# ProDoc_Relay_2025-09-14.net
KiCad netlist of a schematic drawn in EasyEDA Pro
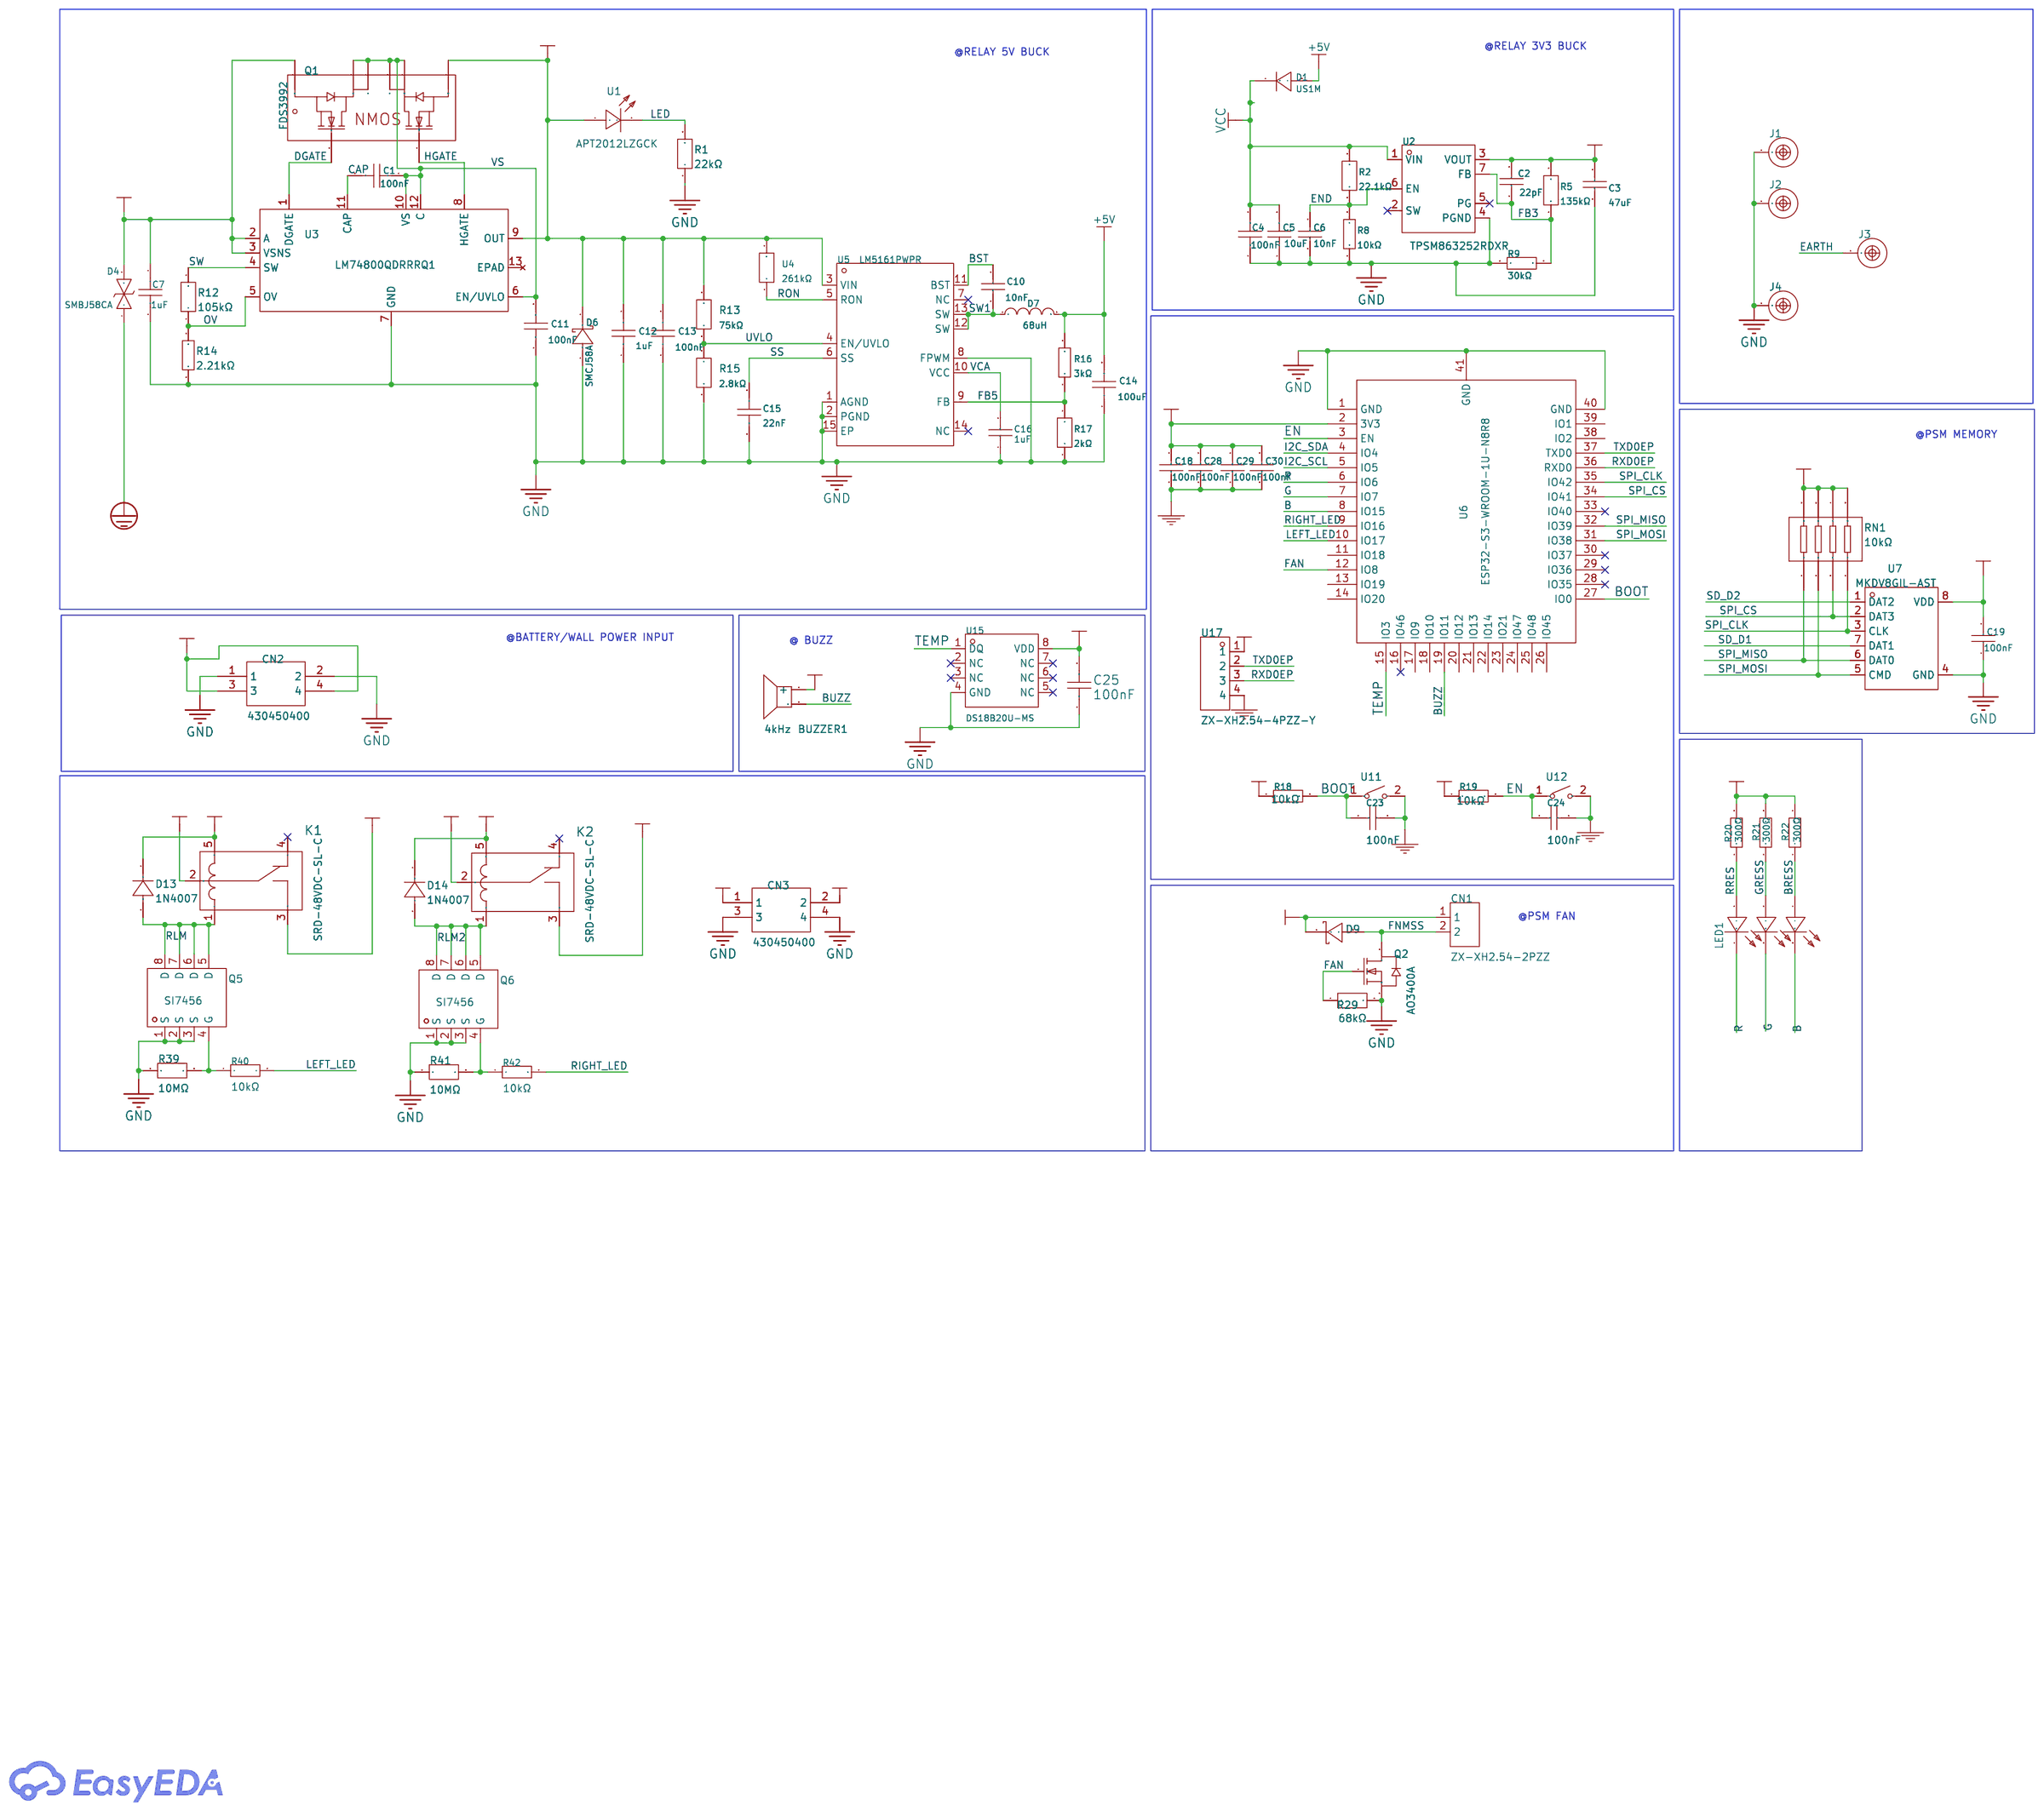
[diagram p0: schematic sheet]

(export (version "E")
  (design (tool "Eeschema 10.0.6"))
  (components
    (comp (ref "BUZZER1")
      (value "4kHz")
      (footprint "easyedapro:BUZ-TH_PKM13EPYH4002-B0")
      (fields
        (field (name "Manufacturer Part") "PKM13EPYH4002-B0")
        (field (name "Manufacturer") "muRata(村田)")
      )
      (libsource (lib "easyedapro") (part "PKM13EPYH4002-B0"))
    )
    (comp (ref "C1")
      (value "100nF")
      (footprint "easyedapro:C1210")
      (fields
        (field (name "Manufacturer Part") "CC1210KKX7RYBB104")
        (field (name "Manufacturer") "YAGEO(国巨)")
      )
      (libsource (lib "easyedapro") (part "CC1210KKX7RYBB104"))
    )
    (comp (ref "C2")
      (value "22pF")
      (footprint "easyedapro:C0201")
      (fields
        (field (name "Manufacturer Part") "GRM0335C1E220JA01D")
        (field (name "Manufacturer") "muRata(村田)")
      )
      (libsource (lib "easyedapro") (part "GRM0335C1E220JA01D"))
    )
    (comp (ref "C3")
      (value "47uF")
      (footprint "easyedapro:C1210")
      (fields
        (field (name "Manufacturer Part") "GRM32ER71A476KE15L")
        (field (name "Manufacturer") "muRata(村田)")
      )
      (libsource (lib "easyedapro") (part "GRM32ER71A476KE15L"))
    )
    (comp (ref "C4")
      (value "100nF")
      (footprint "easyedapro:C0402")
      (fields
        (field (name "Manufacturer Part") "GRM155R71A104KA01D")
        (field (name "Manufacturer") "muRata(村田)")
      )
      (libsource (lib "easyedapro") (part "GRM155R71A104KA01D"))
    )
    (comp (ref "C5")
      (value "10uF")
      (footprint "easyedapro:C0805")
      (fields (field (name "Manufacturer Part") "C0805C106K8PACTU") (field (name "Manufacturer") "KEMET(基美)"))
      (libsource (lib "easyedapro") (part "C0805C106K8PACTU"))
    )
    (comp (ref "C6")
      (value "10nF")
      (footprint "easyedapro:C0201")
      (fields
        (field (name "Manufacturer Part") "GRM033R70J103KA01D")
        (field (name "Manufacturer") "muRata(村田)")
      )
      (libsource (lib "easyedapro") (part "GRM033R70J103KA01D"))
    )
    (comp (ref "C7")
      (value "1uF")
      (footprint "easyedapro:C2220")
      (fields
        (field (name "Manufacturer Part") "GRM55DR72E105KW01L")
        (field (name "Manufacturer") "muRata(村田)")
      )
      (libsource (lib "easyedapro") (part "GRM55DR72E105KW01L"))
    )
    (comp (ref "C10")
      (value "10nF")
      (footprint "easyedapro:C0402")
      (fields
        (field (name "Manufacturer Part") "GRM155R71H103KA88D")
        (field (name "Manufacturer") "muRata(村田)")
      )
      (libsource (lib "easyedapro") (part "GRM155R71H103KA88D"))
    )
    (comp (ref "C11")
      (value "100nF")
      (footprint "easyedapro:C1210")
      (fields
        (field (name "Manufacturer Part") "CC1210KKX7RYBB104")
        (field (name "Manufacturer") "YAGEO(国巨)")
      )
      (libsource (lib "easyedapro") (part "CC1210KKX7RYBB104"))
    )
    (comp (ref "C12")
      (value "1uF")
      (footprint "easyedapro:C2220")
      (fields
        (field (name "Manufacturer Part") "GRM55DR72E105KW01L")
        (field (name "Manufacturer") "muRata(村田)")
      )
      (libsource (lib "easyedapro") (part "GRM55DR72E105KW01L"))
    )
    (comp (ref "C13")
      (value "100nF")
      (footprint "easyedapro:C1210")
      (fields
        (field (name "Manufacturer Part") "CC1210KKX7RYBB104")
        (field (name "Manufacturer") "YAGEO(国巨)")
      )
      (libsource (lib "easyedapro") (part "CC1210KKX7RYBB104"))
    )
    (comp (ref "C14")
      (value "100uF")
      (footprint "easyedapro:C1210")
      (fields
        (field (name "Manufacturer Part") "GRM32ER60J107ME20L")
        (field (name "Manufacturer") "muRata(村田)")
      )
      (libsource (lib "easyedapro") (part "GRM32ER60J107ME20L"))
    )
    (comp (ref "C15")
      (value "22nF")
      (footprint "easyedapro:C0805")
      (fields
        (field (name "Manufacturer Part") "CC0805KRX7R7BB223")
        (field (name "Manufacturer") "YAGEO(国巨)")
      )
      (libsource (lib "easyedapro") (part "CC0805KRX7R7BB223"))
    )
    (comp (ref "C16")
      (value "1uF")
      (footprint "easyedapro:C0603")
      (description "Capacitance:1uF Tolerance:±10% Tolerance:±10% Voltage Rating:16V Temperature Coefficient:X7R")
      (fields
        (field (name "Manufacturer Part") "EMK107B7105KA-T")
        (field (name "Manufacturer") "TAIYO YUDEN(太诱)")
      )
      (libsource (lib "easyedapro") (part "EMK107B7105KA-T"))
    )
    (comp (ref "C18")
      (value "100nF")
      (footprint "easyedapro:C0805")
      (fields (field (name "Manufacturer Part") "0805B104K500NT") (field (name "Manufacturer") "FH(风华)"))
      (libsource (lib "easyedapro") (part "0805B104K500NT"))
    )
    (comp (ref "C19")
      (value "100nF")
      (footprint "easyedapro:C0805")
      (fields (field (name "Manufacturer Part") "0805B104K500NT") (field (name "Manufacturer") "FH(风华)"))
      (libsource (lib "easyedapro") (part "0805B104K500NT"))
    )
    (comp (ref "C23")
      (value "100nF")
      (footprint "easyedapro:C0805")
      (fields (field (name "Manufacturer Part") "0805B104K500NT") (field (name "Manufacturer") "FH(风华)"))
      (libsource (lib "easyedapro") (part "0805B104K500NT"))
    )
    (comp (ref "C24")
      (value "100nF")
      (footprint "easyedapro:C0805")
      (fields (field (name "Manufacturer Part") "0805B104K500NT") (field (name "Manufacturer") "FH(风华)"))
      (libsource (lib "easyedapro") (part "0805B104K500NT"))
    )
    (comp (ref "C25")
      (value "100nF")
      (footprint "easyedapro:C0805")
      (description "Capacitance:0.1uF Tolerance:±10% Tolerance:±10% Voltage Rating:50V Temperature Coefficient:X7R")
      (fields
        (field (name "Manufacturer Part") "GCM21BR71H104KA37K")
        (field (name "Manufacturer") "muRata(村田)")
      )
      (libsource (lib "easyedapro") (part "GCM21BR71H104KA37K"))
    )
    (comp (ref "C28")
      (value "100nF")
      (footprint "easyedapro:C0805")
      (fields (field (name "Manufacturer Part") "0805B104K500NT") (field (name "Manufacturer") "FH(风华)"))
      (libsource (lib "easyedapro") (part "0805B104K500NT"))
    )
    (comp (ref "C29")
      (value "100nF")
      (footprint "easyedapro:C0805")
      (fields (field (name "Manufacturer Part") "0805B104K500NT") (field (name "Manufacturer") "FH(风华)"))
      (libsource (lib "easyedapro") (part "0805B104K500NT"))
    )
    (comp (ref "C30")
      (value "100nF")
      (footprint "easyedapro:C0805")
      (fields (field (name "Manufacturer Part") "0805B104K500NT") (field (name "Manufacturer") "FH(风华)"))
      (libsource (lib "easyedapro") (part "0805B104K500NT"))
    )
    (comp (ref "CN1")
      (value "ZX-XH2.54-2PZZ")
      (footprint "easyedapro:CONN-TH_2P-P2.50_HX25003-2A")
      (fields (field (name "Manufacturer") "Megastar(兆星)"))
      (libsource (lib "easyedapro") (part "ZX-XH2.54-2PZZ"))
    )
    (comp (ref "CN2")
      (value "430450400")
      (footprint "easyedapro:CONN-TH_0430450400")
      (fields (field (name "Manufacturer") "MOLEX"))
      (libsource (lib "easyedapro") (part "0430450400"))
    )
    (comp (ref "CN3")
      (value "430450400")
      (footprint "easyedapro:CONN-TH_0430450400")
      (fields (field (name "Manufacturer") "MOLEX"))
      (libsource (lib "easyedapro") (part "0430450400"))
    )
    (comp (ref "D1")
      (value "US1M")
      (footprint "easyedapro:SMA_L4.4-W2.8-LS5.4-RD")
      (fields (field (name "Manufacturer") "MDD(辰达半导体)"))
      (libsource (lib "easyedapro") (part "US1MG_C412437"))
    )
    (comp (ref "D4")
      (value "SMBJ58CA")
      (footprint "easyedapro:SMB_L4.6-W3.6-LS5.3-BI")
      (fields (field (name "Manufacturer") "AnBon(安邦)"))
      (libsource (lib "easyedapro") (part "SMBJ58CA_C440309"))
    )
    (comp (ref "D6")
      (value "SMCJ58A")
      (footprint "easyedapro:SMC_L6.9-W5.8-LS7.9-RD")
      (fields (field (name "Manufacturer") "宏嘉诚"))
      (libsource (lib "easyedapro") (part "SMCJ58A_C42371547"))
    )
    (comp (ref "D7")
      (value "68uH")
      (footprint "easyedapro:IND-SMD_L12.5-W12.5-SRR1280-150M")
      (fields (field (name "Manufacturer Part") "SRR1260-680M") (field (name "Manufacturer") "BOURNS"))
      (libsource (lib "easyedapro") (part "SRR1260-680M"))
    )
    (comp (ref "D9")
      (value "BAT46WJ,115")
      (footprint "easyedapro:SOD-323F_L2.0-W1.6-LS2.5-RD")
      (fields (field (name "Manufacturer") "Nexperia(安世)"))
      (libsource (lib "easyedapro") (part "BAT46WJ,115"))
    )
    (comp (ref "D13")
      (value "1N4007")
      (footprint "easyedapro:SMA_L4.3-W2.5-LS5.0-RD")
      (fields (field (name "Manufacturer") "TWGMC(迪嘉)"))
      (libsource (lib "easyedapro") (part "1N4007_C727081"))
    )
    (comp (ref "D14")
      (value "1N4007")
      (footprint "easyedapro:SMA_L4.3-W2.5-LS5.0-RD")
      (fields (field (name "Manufacturer") "TWGMC(迪嘉)"))
      (libsource (lib "easyedapro") (part "1N4007_C727081"))
    )
    (comp (ref "J1")
      (value "SCREW-MOUNTING-HOLE-3MM")
      (libsource (lib "easyedapro") (part "SCREW-MOUNTING-HOLE-3MM"))
    )
    (comp (ref "J2")
      (value "SCREW-MOUNTING-HOLE-3MM")
      (libsource (lib "easyedapro") (part "SCREW-MOUNTING-HOLE-3MM"))
    )
    (comp (ref "J3")
      (value "SCREW-MOUNTING-HOLE-3MM")
      (libsource (lib "easyedapro") (part "SCREW-MOUNTING-HOLE-3MM"))
    )
    (comp (ref "J4")
      (value "SCREW-MOUNTING-HOLE-3MM")
      (libsource (lib "easyedapro") (part "SCREW-MOUNTING-HOLE-3MM"))
    )
    (comp (ref "K1")
      (value "SRD-48VDC-SL-C")
      (footprint "easyedapro:RELAY-TH_SRD-48VDC-SL-C")
      (fields (field (name "Manufacturer") "松乐"))
      (libsource (lib "easyedapro") (part "SRD-48VDC-SL-C"))
    )
    (comp (ref "K2")
      (value "SRD-48VDC-SL-C")
      (footprint "easyedapro:RELAY-TH_SRD-48VDC-SL-C")
      (fields (field (name "Manufacturer") "松乐"))
      (libsource (lib "easyedapro") (part "SRD-48VDC-SL-C"))
    )
    (comp (ref "LED1")
      (value "HL-AF-5060H271BU46FU79GC-S1-THL")
      (footprint "easyedapro:LED-ARRAY-SMD_6P-L5.4-W5.0-TL-FD")
      (fields (field (name "Manufacturer") "HONGLITRONIC(鸿利光电)"))
      (libsource (lib "easyedapro") (part "HL-AF-5060H271BU46FU79GC-S1-THL"))
    )
    (comp (ref "Q1")
      (value "FDS3992")
      (footprint "easyedapro:SO-8_L4.9-W3.9-P1.27-LS5.9-BL")
      (fields (field (name "Manufacturer") "onsemi(安森美)"))
      (libsource (lib "easyedapro") (part "FDS3992"))
    )
    (comp (ref "Q2")
      (value "AO3400A")
      (footprint "easyedapro:SOT-23-3_L2.9-W1.6-P1.90-LS2.8-BR")
      (fields (field (name "Manufacturer") "MSKSEMI(美森科)"))
      (libsource (lib "easyedapro") (part "AO3400A_C5379092"))
    )
    (comp (ref "Q5")
      (value "SI7456")
      (footprint "easyedapro:POWERPAK-SO-8_L5.9-W4.9-P1.27-LS6.2-BL")
      (fields (field (name "Manufacturer") "VISHAY(威世)"))
      (libsource (lib "easyedapro") (part "SI7456DP-T1-GE3"))
    )
    (comp (ref "Q6")
      (value "SI7456")
      (footprint "easyedapro:POWERPAK-SO-8_L5.9-W4.9-P1.27-LS6.2-BL")
      (fields (field (name "Manufacturer") "VISHAY(威世)"))
      (libsource (lib "easyedapro") (part "SI7456DP-T1-GE3"))
    )
    (comp (ref "R1")
      (value "22kΩ")
      (footprint "easyedapro:R1210")
      (fields (field (name "Manufacturer Part") "AC1210FR-0722KL") (field (name "Manufacturer") "YAGEO(国巨)"))
      (libsource (lib "easyedapro") (part "AC1210FR-0722KL"))
    )
    (comp (ref "R2")
      (value "22.1kΩ")
      (footprint "easyedapro:R0402")
      (fields
        (field (name "Manufacturer Part") "CRCW040222K1FKED")
        (field (name "Manufacturer") "VISHAY(威世)")
      )
      (libsource (lib "easyedapro") (part "CRCW040222K1FKED"))
    )
    (comp (ref "R5")
      (value "135kΩ")
      (footprint "easyedapro:R0603")
      (fields (field (name "Manufacturer Part") "RT0603BRD07135KL") (field (name "Manufacturer") "YAGEO(国巨)"))
      (libsource (lib "easyedapro") (part "RT0603BRD07135KL"))
    )
    (comp (ref "R8")
      (value "10kΩ")
      (footprint "easyedapro:R0402")
      (fields
        (field (name "Manufacturer Part") "CRCW040210K0FKED")
        (field (name "Manufacturer") "VISHAY(威世)")
      )
      (libsource (lib "easyedapro") (part "CRCW040210K0FKED"))
    )
    (comp (ref "R9")
      (value "30kΩ")
      (footprint "easyedapro:R0603")
      (fields (field (name "Manufacturer Part") "RC0603FR-0730KL") (field (name "Manufacturer") "YAGEO(国巨)"))
      (libsource (lib "easyedapro") (part "RC0603FR-0730KL"))
    )
    (comp (ref "R12")
      (value "105kΩ")
      (footprint "easyedapro:R1206")
      (fields (field (name "Manufacturer Part") "RC1206FR-07105KL") (field (name "Manufacturer") "YAGEO(国巨)"))
      (libsource (lib "easyedapro") (part "RC1206FR-07105KL"))
    )
    (comp (ref "R13")
      (value "75kΩ")
      (footprint "easyedapro:R1210")
      (fields (field (name "Manufacturer Part") "AC1210FR-0775KL") (field (name "Manufacturer") "YAGEO(国巨)"))
      (libsource (lib "easyedapro") (part "AC1210FR-0775KL"))
    )
    (comp (ref "R14")
      (value "2.21kΩ")
      (footprint "easyedapro:R1206")
      (fields (field (name "Manufacturer Part") "AC1206FR-072K21L") (field (name "Manufacturer") "YAGEO(国巨)"))
      (libsource (lib "easyedapro") (part "AC1206FR-072K21L"))
    )
    (comp (ref "R15")
      (value "2.8kΩ")
      (footprint "easyedapro:R1210")
      (fields (field (name "Manufacturer Part") "AC1210FR-072K8L") (field (name "Manufacturer") "YAGEO(国巨)"))
      (libsource (lib "easyedapro") (part "AC1210FR-072K8L"))
    )
    (comp (ref "R16")
      (value "3kΩ")
      (footprint "easyedapro:R0603")
      (fields (field (name "Manufacturer Part") "RC0603FR-073KL") (field (name "Manufacturer") "YAGEO(国巨)"))
      (libsource (lib "easyedapro") (part "RC0603FR-073KL"))
    )
    (comp (ref "R17")
      (value "2kΩ")
      (footprint "easyedapro:R0402")
      (fields
        (field (name "Manufacturer Part") "CRCW04022K00FKED")
        (field (name "Manufacturer") "VISHAY(威世)")
      )
      (libsource (lib "easyedapro") (part "CRCW04022K00FKED"))
    )
    (comp (ref "R18")
      (value "10kΩ")
      (footprint "easyedapro:R0805")
      (fields
        (field (name "Manufacturer Part") "0805W8F1002T5E")
        (field (name "Manufacturer") "UNI-ROYAL(厚声)")
      )
      (libsource (lib "easyedapro") (part "0805W8F1002T5E"))
    )
    (comp (ref "R19")
      (value "10kΩ")
      (footprint "easyedapro:R0805")
      (fields
        (field (name "Manufacturer Part") "0805W8F1002T5E")
        (field (name "Manufacturer") "UNI-ROYAL(厚声)")
      )
      (libsource (lib "easyedapro") (part "0805W8F1002T5E"))
    )
    (comp (ref "R20")
      (value "300Ω")
      (footprint "easyedapro:R0805")
      (fields
        (field (name "Manufacturer Part") "0805W8F3000T5E")
        (field (name "Manufacturer") "UNI-ROYAL(厚声)")
      )
      (libsource (lib "easyedapro") (part "0805W8F3000T5E"))
    )
    (comp (ref "R21")
      (value "300Ω")
      (footprint "easyedapro:R0805")
      (fields
        (field (name "Manufacturer Part") "0805W8F3000T5E")
        (field (name "Manufacturer") "UNI-ROYAL(厚声)")
      )
      (libsource (lib "easyedapro") (part "0805W8F3000T5E"))
    )
    (comp (ref "R22")
      (value "300Ω")
      (footprint "easyedapro:R0805")
      (fields
        (field (name "Manufacturer Part") "0805W8F3000T5E")
        (field (name "Manufacturer") "UNI-ROYAL(厚声)")
      )
      (libsource (lib "easyedapro") (part "0805W8F3000T5E"))
    )
    (comp (ref "R29")
      (value "68kΩ")
      (footprint "easyedapro:R1206")
      (fields (field (name "Manufacturer Part") "RT1206BRD0768KL") (field (name "Manufacturer") "YAGEO(国巨)"))
      (libsource (lib "easyedapro") (part "RT1206BRD0768KL"))
    )
    (comp (ref "R39")
      (value "10MΩ")
      (footprint "easyedapro:R1206")
      (fields (field (name "Manufacturer Part") "FRC1206F1005TS") (field (name "Manufacturer") "FOJAN(富捷)"))
      (libsource (lib "easyedapro") (part "FRC1206F1005TS"))
    )
    (comp (ref "R40")
      (value "10kΩ")
      (footprint "easyedapro:R1206")
      (fields
        (field (name "Manufacturer Part") "1206W4F1002T5E")
        (field (name "Manufacturer") "UNI-ROYAL(厚声)")
      )
      (libsource (lib "easyedapro") (part "1206W4F1002T5E"))
    )
    (comp (ref "R41")
      (value "10MΩ")
      (footprint "easyedapro:R1206")
      (fields (field (name "Manufacturer Part") "FRC1206F1005TS") (field (name "Manufacturer") "FOJAN(富捷)"))
      (libsource (lib "easyedapro") (part "FRC1206F1005TS"))
    )
    (comp (ref "R42")
      (value "10kΩ")
      (footprint "easyedapro:R1206")
      (fields
        (field (name "Manufacturer Part") "1206W4F1002T5E")
        (field (name "Manufacturer") "UNI-ROYAL(厚声)")
      )
      (libsource (lib "easyedapro") (part "1206W4F1002T5E"))
    )
    (comp (ref "RN1")
      (value "10kΩ")
      (footprint "easyedapro:RES-ARRAY-SMD_0603-8P-L3.2-W1.6-BL")
      (fields
        (field (name "Manufacturer Part") "4D03WGJ0103T5E")
        (field (name "Manufacturer") "UNI-ROYAL(厚声)")
      )
      (libsource (lib "easyedapro") (part "4D03WGJ0103T5E"))
    )
    (comp (ref "U1")
      (value "APT2012LZGCK")
      (footprint "easyedapro:LED-SMD_L2.0-W1.3-R-RD")
      (fields (field (name "Manufacturer") "Kingbright"))
      (libsource (lib "easyedapro") (part "APT2012LZGCK"))
    )
    (comp (ref "U2")
      (value "TPSM863252RDXR")
      (footprint "easyedapro:QFN-7_L4.0-W3.3_TPSM863257RDXR")
      (fields (field (name "Manufacturer") "TI(德州仪器)"))
      (libsource (lib "easyedapro") (part "TPSM863252RDXR"))
    )
    (comp (ref "U3")
      (value "LM74800QDRRRQ1")
      (footprint "easyedapro:WSON-12_L3.0-W3.0-P0.50-TL-EP-2")
      (fields (field (name "Manufacturer") "TI(德州仪器)"))
      (libsource (lib "easyedapro") (part "LM74800QDRRRQ1"))
    )
    (comp (ref "U4")
      (value "261kΩ")
      (footprint "easyedapro:R0402")
      (fields
        (field (name "Manufacturer Part") "CRCW0402261KFKED")
        (field (name "Manufacturer") "VISHAY(威世)")
      )
      (libsource (lib "easyedapro") (part "CRCW0402261KFKED"))
    )
    (comp (ref "U5")
      (value "LM5161PWPR")
      (footprint "easyedapro:HTSSOP-14_L5.0-W4.4-P0.65-LS6.4-BL-EP3.0")
      (fields (field (name "Manufacturer") "TI(德州仪器)"))
      (libsource (lib "easyedapro") (part "LM5161PWPR"))
    )
    (comp (ref "U6")
      (value "ESP32-S3-WROOM-1U-N8R8")
      (footprint "easyedapro:WIRELM-SMD_ESP32-S3-WROOM-1U")
      (fields (field (name "Manufacturer") "ESPRESSIF(乐鑫)"))
      (libsource (lib "easyedapro") (part "ESP32-S3-WROOM-1U-N8R8"))
    )
    (comp (ref "U7")
      (value "MKDV8GIL-AST")
      (footprint "easyedapro:LGA-8_L6.0-W8.0-P1.27-TL")
      (fields (field (name "Manufacturer") "MK(米客方德)"))
      (libsource (lib "easyedapro") (part "MKDV8GIL-AST"))
    )
    (comp (ref "U11") (value "TD-1183SN-1.7H-250") (libsource (lib "easyedapro") (part "TD-1183SN-1.7H-250")))
    (comp (ref "U12") (value "TD-1183SN-1.7H-250") (libsource (lib "easyedapro") (part "TD-1183SN-1.7H-250")))
    (comp (ref "U15")
      (value "DS18B20U-MS")
      (footprint "easyedapro:MSOP-8_L3.0-W3.0-P0.65-LS4.9-BL-1")
      (fields (field (name "Manufacturer") "MSKSEMI(美森科)"))
      (libsource (lib "easyedapro") (part "DS18B20U-MS"))
    )
    (comp (ref "U17")
      (value "ZX-XH2.54-4PZZ-Y")
      (footprint "easyedapro:CONN-TH_4P-P2.50_ZX-XH2.54-4PZZ-Y")
      (fields (field (name "Manufacturer") "Megastar(兆星)"))
      (libsource (lib "easyedapro") (part "ZX-XH2.54-4PZZ-Y"))
    )
  )
  (nets
    (net (code "1") (name "+3V3") (class "Default")
      (node (ref "BUZZER1") (pin "1") (pinfunction "+_1") (pintype "unspecified"))
      (node (ref "C18") (pin "2") (pinfunction "2_2") (pintype "input"))
      (node (ref "C19") (pin "2") (pinfunction "2_2") (pintype "input"))
      (node (ref "C2") (pin "2") (pinfunction "2_2") (pintype "input"))
      (node (ref "C25") (pin "2") (pinfunction "2_2") (pintype "unspecified"))
      (node (ref "C28") (pin "2") (pinfunction "2_2") (pintype "input"))
      (node (ref "C29") (pin "2") (pinfunction "2_2") (pintype "input"))
      (node (ref "C3") (pin "2") (pinfunction "2_2") (pintype "input"))
      (node (ref "C30") (pin "2") (pinfunction "2_2") (pintype "input"))
      (node (ref "R18") (pin "1") (pinfunction "1_1") (pintype "input"))
      (node (ref "R19") (pin "1") (pinfunction "1_1") (pintype "input"))
      (node (ref "R20") (pin "2") (pinfunction "2_2") (pintype "input"))
      (node (ref "R21") (pin "2") (pinfunction "2_2") (pintype "input"))
      (node (ref "R22") (pin "2") (pinfunction "2_2") (pintype "input"))
      (node (ref "R5") (pin "2") (pinfunction "2_2") (pintype "unspecified"))
      (node (ref "RN1") (pin "5") (pinfunction "5_5") (pintype "input"))
      (node (ref "RN1") (pin "6") (pinfunction "6_6") (pintype "input"))
      (node (ref "RN1") (pin "7") (pinfunction "7_7") (pintype "input"))
      (node (ref "RN1") (pin "8") (pinfunction "8_8") (pintype "input"))
      (node (ref "U15") (pin "8") (pinfunction "VDD_8") (pintype "unspecified"))
      (node (ref "U17") (pin "1") (pinfunction "1_1") (pintype "unspecified"))
      (node (ref "U2") (pin "3") (pinfunction "VOUT_3") (pintype "unspecified"))
      (node (ref "U6") (pin "2") (pinfunction "3V3_2") (pintype "unspecified"))
      (node (ref "U7") (pin "8") (pinfunction "VDD_8") (pintype "unspecified"))
    )
    (net (code "2") (name "+5V") (class "Default")
      (node (ref "C14") (pin "2") (pinfunction "2_2") (pintype "input"))
      (node (ref "D1") (pin "2") (pinfunction "A_2") (pintype "unspecified"))
      (node (ref "D7") (pin "2") (pinfunction "2_2") (pintype "unspecified"))
      (node (ref "R16") (pin "2") (pinfunction "2_2") (pintype "input"))
    )
    (net (code "3") (name "+48V") (class "Default")
      (node (ref "C12") (pin "2") (pinfunction "2_2") (pintype "input"))
      (node (ref "C13") (pin "2") (pinfunction "2_2") (pintype "unspecified"))
      (node (ref "D13") (pin "1") (pinfunction "K_1") (pintype "unspecified"))
      (node (ref "D14") (pin "1") (pinfunction "K_1") (pintype "unspecified"))
      (node (ref "D6") (pin "1") (pinfunction "K_1") (pintype "unspecified"))
      (node (ref "K1") (pin "2") (pinfunction "2_2") (pintype "input"))
      (node (ref "K1") (pin "5") (pinfunction "5_5") (pintype "input"))
      (node (ref "K2") (pin "2") (pinfunction "2_2") (pintype "input"))
      (node (ref "K2") (pin "5") (pinfunction "5_5") (pintype "input"))
      (node (ref "Q1") (pin "3") (pinfunction "S2_3") (pintype "unspecified"))
      (node (ref "R13") (pin "2") (pinfunction "2_2") (pintype "input"))
      (node (ref "U1") (pin "1") (pinfunction "A_1") (pintype "unspecified"))
      (node (ref "U3") (pin "9") (pinfunction "OUT_9") (pintype "unspecified"))
      (node (ref "U4") (pin "2") (pinfunction "2_2") (pintype "unspecified"))
      (node (ref "U5") (pin "3") (pinfunction "VIN_3") (pintype "unspecified"))
    )
    (net (code "4") (name "/B") (class "Default")
      (node (ref "LED1") (pin "6") (pinfunction "C_6") (pintype "unspecified"))
      (node (ref "U6") (pin "8") (pinfunction "IO15_8") (pintype "unspecified"))
    )
    (net (code "5") (name "/BOOT") (class "Default")
      (node (ref "C23") (pin "1") (pinfunction "1_1") (pintype "input"))
      (node (ref "R18") (pin "2") (pinfunction "2_2") (pintype "input"))
      (node (ref "U11") (pin "1") (pinfunction "1_1") (pintype "unspecified"))
      (node (ref "U6") (pin "27") (pinfunction "IO0_27") (pintype "unspecified"))
    )
    (net (code "6") (name "/BRESS") (class "Default")
      (node (ref "LED1") (pin "1") (pinfunction "A_1") (pintype "unspecified"))
      (node (ref "R22") (pin "1") (pinfunction "1_1") (pintype "input"))
    )
    (net (code "7") (name "/BST") (class "Default")
      (node (ref "C10") (pin "2") (pinfunction "2_2") (pintype "input"))
      (node (ref "U5") (pin "11") (pinfunction "BST_11") (pintype "unspecified"))
    )
    (net (code "8") (name "/BUZZ") (class "Default")
      (node (ref "BUZZER1") (pin "2") (pinfunction "2_2") (pintype "unspecified"))
      (node (ref "U6") (pin "19") (pinfunction "IO11_19") (pintype "unspecified"))
    )
    (net (code "9") (name "/CAP") (class "Default")
      (node (ref "C1") (pin "2") (pinfunction "2_2") (pintype "unspecified"))
      (node (ref "U3") (pin "11") (pinfunction "CAP_11") (pintype "unspecified"))
    )
    (net (code "10") (name "/DGATE") (class "Default")
      (node (ref "Q1") (pin "2") (pinfunction "G1_2") (pintype "unspecified"))
      (node (ref "U3") (pin "1") (pinfunction "DGATE_1") (pintype "unspecified"))
    )
    (net (code "11") (name "/EN") (class "Default")
      (node (ref "C24") (pin "1") (pinfunction "1_1") (pintype "input"))
      (node (ref "R19") (pin "2") (pinfunction "2_2") (pintype "input"))
      (node (ref "U12") (pin "1") (pinfunction "1_1") (pintype "unspecified"))
      (node (ref "U6") (pin "3") (pinfunction "EN_3") (pintype "unspecified"))
    )
    (net (code "12") (name "/END") (class "Default")
      (node (ref "C6") (pin "2") (pinfunction "2_2") (pintype "input"))
      (node (ref "R2") (pin "1") (pinfunction "1_1") (pintype "unspecified"))
      (node (ref "R8") (pin "2") (pinfunction "2_2") (pintype "unspecified"))
      (node (ref "U2") (pin "6") (pinfunction "EN_6") (pintype "unspecified"))
    )
    (net (code "13") (name "/FAN") (class "Default")
      (node (ref "Q2") (pin "1") (pinfunction "G_1") (pintype "unspecified"))
      (node (ref "R29") (pin "1") (pinfunction "1_1") (pintype "unspecified"))
      (node (ref "U6") (pin "12") (pinfunction "IO8_12") (pintype "unspecified"))
    )
    (net (code "14") (name "/FB3") (class "Default")
      (node (ref "C2") (pin "1") (pinfunction "1_1") (pintype "input"))
      (node (ref "R5") (pin "1") (pinfunction "1_1") (pintype "unspecified"))
      (node (ref "R9") (pin "2") (pinfunction "2_2") (pintype "input"))
      (node (ref "U2") (pin "7") (pinfunction "FB_7") (pintype "unspecified"))
    )
    (net (code "15") (name "/FB5") (class "Default")
      (node (ref "R16") (pin "1") (pinfunction "1_1") (pintype "input"))
      (node (ref "R17") (pin "2") (pinfunction "2_2") (pintype "input"))
      (node (ref "U5") (pin "9") (pinfunction "FB_9") (pintype "unspecified"))
    )
    (net (code "16") (name "/FNMSS") (class "Default")
      (node (ref "CN1") (pin "2") (pinfunction "2_2") (pintype "unspecified"))
      (node (ref "D9") (pin "2") (pinfunction "A_2") (pintype "unspecified"))
      (node (ref "Q2") (pin "3") (pinfunction "D_3") (pintype "unspecified"))
    )
    (net (code "17") (name "/G") (class "Default")
      (node (ref "LED1") (pin "5") (pinfunction "C_5") (pintype "unspecified"))
      (node (ref "U6") (pin "7") (pinfunction "IO7_7") (pintype "unspecified"))
    )
    (net (code "18") (name "/GRESS") (class "Default")
      (node (ref "LED1") (pin "2") (pinfunction "A_2") (pintype "unspecified"))
      (node (ref "R21") (pin "1") (pinfunction "1_1") (pintype "input"))
    )
    (net (code "19") (name "/HGATE") (class "Default")
      (node (ref "Q1") (pin "4") (pinfunction "G2_4") (pintype "unspecified"))
      (node (ref "U3") (pin "8") (pinfunction "HGATE_8") (pintype "unspecified"))
    )
    (net (code "20") (name "/I2C_SCL") (class "Default")
      (node (ref "U6") (pin "5") (pinfunction "IO5_5") (pintype "unspecified"))
    )
    (net (code "21") (name "/I2C_SDA") (class "Default")
      (node (ref "U6") (pin "4") (pinfunction "IO4_4") (pintype "unspecified"))
    )
    (net (code "22") (name "/LED") (class "Default")
      (node (ref "R1") (pin "2") (pinfunction "2_2") (pintype "unspecified"))
      (node (ref "U1") (pin "2") (pinfunction "K_2") (pintype "unspecified"))
    )
    (net (code "23") (name "/LEFT_LED") (class "Default")
      (node (ref "R40") (pin "2") (pinfunction "2_2") (pintype "input"))
      (node (ref "U6") (pin "10") (pinfunction "IO17_10") (pintype "unspecified"))
    )
    (net (code "24") (name "/OV") (class "Default")
      (node (ref "R12") (pin "1") (pinfunction "1_1") (pintype "unspecified"))
      (node (ref "R14") (pin "2") (pinfunction "2_2") (pintype "unspecified"))
      (node (ref "U3") (pin "5") (pinfunction "OV_5") (pintype "unspecified"))
    )
    (net (code "25") (name "/R") (class "Default")
      (node (ref "LED1") (pin "4") (pinfunction "C_4") (pintype "unspecified"))
      (node (ref "U6") (pin "6") (pinfunction "IO6_6") (pintype "unspecified"))
    )
    (net (code "26") (name "/RIGHT_LED") (class "Default")
      (node (ref "R42") (pin "2") (pinfunction "2_2") (pintype "input"))
      (node (ref "U6") (pin "9") (pinfunction "IO16_9") (pintype "unspecified"))
    )
    (net (code "27") (name "/RLM") (class "Default")
      (node (ref "D13") (pin "2") (pinfunction "A_2") (pintype "unspecified"))
      (node (ref "K1") (pin "1") (pinfunction "1_1") (pintype "input"))
      (node (ref "Q5") (pin "5") (pinfunction "D_5") (pintype "unspecified"))
      (node (ref "Q5") (pin "6") (pinfunction "D_6") (pintype "unspecified"))
      (node (ref "Q5") (pin "7") (pinfunction "D_7") (pintype "unspecified"))
      (node (ref "Q5") (pin "8") (pinfunction "D_8") (pintype "unspecified"))
    )
    (net (code "28") (name "/RLM2") (class "Default")
      (node (ref "D14") (pin "2") (pinfunction "A_2") (pintype "unspecified"))
      (node (ref "K2") (pin "1") (pinfunction "1_1") (pintype "input"))
      (node (ref "Q6") (pin "5") (pinfunction "D_5") (pintype "unspecified"))
      (node (ref "Q6") (pin "6") (pinfunction "D_6") (pintype "unspecified"))
      (node (ref "Q6") (pin "7") (pinfunction "D_7") (pintype "unspecified"))
      (node (ref "Q6") (pin "8") (pinfunction "D_8") (pintype "unspecified"))
    )
    (net (code "29") (name "/RON") (class "Default")
      (node (ref "U4") (pin "1") (pinfunction "1_1") (pintype "unspecified"))
      (node (ref "U5") (pin "5") (pinfunction "RON_5") (pintype "unspecified"))
    )
    (net (code "30") (name "/RRES") (class "Default")
      (node (ref "LED1") (pin "3") (pinfunction "A_3") (pintype "unspecified"))
      (node (ref "R20") (pin "1") (pinfunction "1_1") (pintype "input"))
    )
    (net (code "31") (name "/RXD0EP") (class "Default")
      (node (ref "U17") (pin "3") (pinfunction "3_3") (pintype "unspecified"))
      (node (ref "U6") (pin "36") (pinfunction "RXD0_36") (pintype "unspecified"))
    )
    (net (code "32") (name "/SD_D1") (class "Default")
      (node (ref "U7") (pin "7") (pinfunction "DAT1_7") (pintype "unspecified"))
    )
    (net (code "33") (name "/SD_D2") (class "Default")
      (node (ref "U7") (pin "1") (pinfunction "DAT2_1") (pintype "unspecified"))
    )
    (net (code "34") (name "/SPI_CLK") (class "Default")
      (node (ref "RN1") (pin "1") (pinfunction "1_1") (pintype "input"))
      (node (ref "U6") (pin "35") (pinfunction "IO42_35") (pintype "unspecified"))
      (node (ref "U7") (pin "3") (pinfunction "CLK_3") (pintype "unspecified"))
    )
    (net (code "35") (name "/SPI_CS") (class "Default")
      (node (ref "RN1") (pin "2") (pinfunction "2_2") (pintype "input"))
      (node (ref "U6") (pin "34") (pinfunction "IO41_34") (pintype "unspecified"))
      (node (ref "U7") (pin "2") (pinfunction "DAT3_2") (pintype "unspecified"))
    )
    (net (code "36") (name "/SPI_MISO") (class "Default")
      (node (ref "RN1") (pin "4") (pinfunction "4_4") (pintype "input"))
      (node (ref "U6") (pin "32") (pinfunction "IO39_32") (pintype "unspecified"))
      (node (ref "U7") (pin "6") (pinfunction "DAT0_6") (pintype "unspecified"))
    )
    (net (code "37") (name "/SPI_MOSI") (class "Default")
      (node (ref "RN1") (pin "3") (pinfunction "3_3") (pintype "input"))
      (node (ref "U6") (pin "31") (pinfunction "IO38_31") (pintype "unspecified"))
      (node (ref "U7") (pin "5") (pinfunction "CMD_5") (pintype "unspecified"))
    )
    (net (code "38") (name "/SS") (class "Default")
      (node (ref "C15") (pin "2") (pinfunction "2_2") (pintype "input"))
      (node (ref "U5") (pin "6") (pinfunction "SS_6") (pintype "unspecified"))
    )
    (net (code "39") (name "/SW") (class "Default")
      (node (ref "R12") (pin "2") (pinfunction "2_2") (pintype "unspecified"))
      (node (ref "U3") (pin "4") (pinfunction "SW_4") (pintype "unspecified"))
    )
    (net (code "40") (name "/SW1") (class "Default")
      (node (ref "C10") (pin "1") (pinfunction "1_1") (pintype "input"))
      (node (ref "D7") (pin "1") (pinfunction "1_1") (pintype "unspecified"))
      (node (ref "U5") (pin "12") (pinfunction "SW_12") (pintype "unspecified"))
      (node (ref "U5") (pin "13") (pinfunction "SW_13") (pintype "unspecified"))
    )
    (net (code "41") (name "/TEMP") (class "Default")
      (node (ref "U15") (pin "1") (pinfunction "DQ_1") (pintype "unspecified"))
      (node (ref "U6") (pin "15") (pinfunction "IO3_15") (pintype "unspecified"))
    )
    (net (code "42") (name "/TXD0EP") (class "Default")
      (node (ref "U17") (pin "2") (pinfunction "2_2") (pintype "unspecified"))
      (node (ref "U6") (pin "37") (pinfunction "TXD0_37") (pintype "unspecified"))
    )
    (net (code "43") (name "/UVLO") (class "Default")
      (node (ref "R13") (pin "1") (pinfunction "1_1") (pintype "input"))
      (node (ref "R15") (pin "2") (pinfunction "2_2") (pintype "unspecified"))
      (node (ref "U5") (pin "4") (pinfunction "EN/UVLO_4") (pintype "unspecified"))
    )
    (net (code "44") (name "/VCA") (class "Default")
      (node (ref "C16") (pin "2") (pinfunction "2_2") (pintype "input"))
      (node (ref "U5") (pin "10") (pinfunction "VCC_10") (pintype "unspecified"))
    )
    (net (code "45") (name "/VS") (class "Default")
      (node (ref "C1") (pin "1") (pinfunction "1_1") (pintype "unspecified"))
      (node (ref "C11") (pin "2") (pinfunction "2_2") (pintype "unspecified"))
      (node (ref "Q1") (pin "5") (pinfunction "D2_5") (pintype "unspecified"))
      (node (ref "Q1") (pin "6") (pinfunction "D2_6") (pintype "unspecified"))
      (node (ref "Q1") (pin "7") (pinfunction "D1_7") (pintype "unspecified"))
      (node (ref "Q1") (pin "8") (pinfunction "D1_8") (pintype "unspecified"))
      (node (ref "U3") (pin "10") (pinfunction "VS_10") (pintype "unspecified"))
      (node (ref "U3") (pin "12") (pinfunction "C_12") (pintype "unspecified"))
      (node (ref "U3") (pin "6") (pinfunction "EN/UVLO_6") (pintype "unspecified"))
    )
    (net (code "46") (name "EARTH") (class "Default")
      (node (ref "D4") (pin "1") (pinfunction "1_1") (pintype "unspecified"))
      (node (ref "J3") (pin "1") (pinfunction "1_1") (pintype "unspecified"))
    )
    (net (code "47") (name "GND") (class "Default")
      (node (ref "C11") (pin "1") (pinfunction "1_1") (pintype "unspecified"))
      (node (ref "C12") (pin "1") (pinfunction "1_1") (pintype "input"))
      (node (ref "C13") (pin "1") (pinfunction "1_1") (pintype "unspecified"))
      (node (ref "C14") (pin "1") (pinfunction "1_1") (pintype "input"))
      (node (ref "C15") (pin "1") (pinfunction "1_1") (pintype "input"))
      (node (ref "C16") (pin "1") (pinfunction "1_1") (pintype "input"))
      (node (ref "C18") (pin "1") (pinfunction "1_1") (pintype "input"))
      (node (ref "C19") (pin "1") (pinfunction "1_1") (pintype "input"))
      (node (ref "C23") (pin "2") (pinfunction "2_2") (pintype "input"))
      (node (ref "C24") (pin "2") (pinfunction "2_2") (pintype "input"))
      (node (ref "C25") (pin "1") (pinfunction "1_1") (pintype "unspecified"))
      (node (ref "C28") (pin "1") (pinfunction "1_1") (pintype "input"))
      (node (ref "C29") (pin "1") (pinfunction "1_1") (pintype "input"))
      (node (ref "C3") (pin "1") (pinfunction "1_1") (pintype "input"))
      (node (ref "C30") (pin "1") (pinfunction "1_1") (pintype "input"))
      (node (ref "C4") (pin "1") (pinfunction "1_1") (pintype "input"))
      (node (ref "C5") (pin "1") (pinfunction "1_1") (pintype "unspecified"))
      (node (ref "C6") (pin "1") (pinfunction "1_1") (pintype "input"))
      (node (ref "C7") (pin "2") (pinfunction "2_2") (pintype "input"))
      (node (ref "CN2") (pin "1") (pinfunction "1_1") (pintype "unspecified"))
      (node (ref "CN2") (pin "2") (pinfunction "2_2") (pintype "unspecified"))
      (node (ref "CN3") (pin "3") (pinfunction "3_3") (pintype "unspecified"))
      (node (ref "CN3") (pin "4") (pinfunction "4_4") (pintype "unspecified"))
      (node (ref "D6") (pin "2") (pinfunction "A_2") (pintype "unspecified"))
      (node (ref "J1") (pin "1") (pinfunction "1_1") (pintype "unspecified"))
      (node (ref "J2") (pin "1") (pinfunction "1_1") (pintype "unspecified"))
      (node (ref "J4") (pin "1") (pinfunction "1_1") (pintype "unspecified"))
      (node (ref "Q2") (pin "2") (pinfunction "S_2") (pintype "unspecified"))
      (node (ref "Q5") (pin "1") (pinfunction "S_1") (pintype "unspecified"))
      (node (ref "Q5") (pin "2") (pinfunction "S_2") (pintype "unspecified"))
      (node (ref "Q5") (pin "3") (pinfunction "S_3") (pintype "unspecified"))
      (node (ref "Q6") (pin "1") (pinfunction "S_1") (pintype "unspecified"))
      (node (ref "Q6") (pin "2") (pinfunction "S_2") (pintype "unspecified"))
      (node (ref "Q6") (pin "3") (pinfunction "S_3") (pintype "unspecified"))
      (node (ref "R1") (pin "1") (pinfunction "1_1") (pintype "unspecified"))
      (node (ref "R14") (pin "1") (pinfunction "1_1") (pintype "unspecified"))
      (node (ref "R15") (pin "1") (pinfunction "1_1") (pintype "unspecified"))
      (node (ref "R17") (pin "1") (pinfunction "1_1") (pintype "input"))
      (node (ref "R29") (pin "2") (pinfunction "2_2") (pintype "unspecified"))
      (node (ref "R39") (pin "1") (pinfunction "1_1") (pintype "unspecified"))
      (node (ref "R41") (pin "1") (pinfunction "1_1") (pintype "unspecified"))
      (node (ref "R8") (pin "1") (pinfunction "1_1") (pintype "unspecified"))
      (node (ref "R9") (pin "1") (pinfunction "1_1") (pintype "input"))
      (node (ref "U11") (pin "2") (pinfunction "2_2") (pintype "unspecified"))
      (node (ref "U12") (pin "2") (pinfunction "2_2") (pintype "unspecified"))
      (node (ref "U15") (pin "4") (pinfunction "GND_4") (pintype "unspecified"))
      (node (ref "U17") (pin "4") (pinfunction "4_4") (pintype "unspecified"))
      (node (ref "U2") (pin "4") (pinfunction "PGND_4") (pintype "unspecified"))
      (node (ref "U3") (pin "7") (pinfunction "GND_7") (pintype "unspecified"))
      (node (ref "U5") (pin "1") (pinfunction "AGND_1") (pintype "unspecified"))
      (node (ref "U5") (pin "15") (pinfunction "EP_15") (pintype "unspecified"))
      (node (ref "U5") (pin "2") (pinfunction "PGND_2") (pintype "unspecified"))
      (node (ref "U5") (pin "8") (pinfunction "FPWM_8") (pintype "unspecified"))
      (node (ref "U6") (pin "1") (pinfunction "GND_1") (pintype "unspecified"))
      (node (ref "U6") (pin "40") (pinfunction "GND_40") (pintype "unspecified"))
      (node (ref "U6") (pin "41") (pinfunction "GND_41") (pintype "unspecified"))
      (node (ref "U7") (pin "4") (pinfunction "GND_4") (pintype "unspecified"))
    )
    (net (code "48") (name "Net-(Q5-G)") (class "Default")
      (node (ref "Q5") (pin "4") (pinfunction "G_4") (pintype "unspecified"))
      (node (ref "R39") (pin "2") (pinfunction "2_2") (pintype "unspecified"))
      (node (ref "R40") (pin "1") (pinfunction "1_1") (pintype "input"))
    )
    (net (code "49") (name "Net-(Q6-G)") (class "Default")
      (node (ref "Q6") (pin "4") (pinfunction "G_4") (pintype "unspecified"))
      (node (ref "R41") (pin "2") (pinfunction "2_2") (pintype "unspecified"))
      (node (ref "R42") (pin "1") (pinfunction "1_1") (pintype "input"))
    )
    (net (code "50") (name "PW_LEFT") (class "Default")
      (node (ref "CN3") (pin "1") (pinfunction "1_1") (pintype "unspecified"))
      (node (ref "K1") (pin "3") (pinfunction "3_3") (pintype "input"))
    )
    (net (code "51") (name "PW_RIGHT") (class "Default")
      (node (ref "CN3") (pin "2") (pinfunction "2_2") (pintype "unspecified"))
      (node (ref "K2") (pin "3") (pinfunction "3_3") (pintype "input"))
    )
    (net (code "52") (name "VCC") (class "Default")
      (node (ref "C4") (pin "2") (pinfunction "2_2") (pintype "input"))
      (node (ref "C5") (pin "2") (pinfunction "2_2") (pintype "unspecified"))
      (node (ref "D1") (pin "1") (pinfunction "C_1") (pintype "unspecified"))
      (node (ref "R2") (pin "2") (pinfunction "2_2") (pintype "unspecified"))
      (node (ref "U2") (pin "1") (pinfunction "VIN_1") (pintype "unspecified"))
    )
    (net (code "53") (name "VIN") (class "Default")
      (node (ref "C7") (pin "1") (pinfunction "1_1") (pintype "input"))
      (node (ref "CN1") (pin "1") (pinfunction "1_1") (pintype "unspecified"))
      (node (ref "CN2") (pin "3") (pinfunction "3_3") (pintype "unspecified"))
      (node (ref "CN2") (pin "4") (pinfunction "4_4") (pintype "unspecified"))
      (node (ref "D4") (pin "2") (pinfunction "2_2") (pintype "unspecified"))
      (node (ref "D9") (pin "1") (pinfunction "K_1") (pintype "unspecified"))
      (node (ref "Q1") (pin "1") (pinfunction "S1_1") (pintype "unspecified"))
      (node (ref "U3") (pin "2") (pinfunction "A_2") (pintype "unspecified"))
      (node (ref "U3") (pin "3") (pinfunction "VSNS_3") (pintype "unspecified"))
    )
    (net (code "54") (name "unconnected-(K1-Pad4)") (class "Default")
      (node (ref "K1") (pin "4") (pinfunction "4_4") (pintype "input+no_connect"))
    )
    (net (code "55") (name "unconnected-(K2-Pad4)") (class "Default")
      (node (ref "K2") (pin "4") (pinfunction "4_4") (pintype "input+no_connect"))
    )
    (net (code "56") (name "unconnected-(U2-PG-Pad5)") (class "Default")
      (node (ref "U2") (pin "5") (pinfunction "PG_5") (pintype "unspecified+no_connect"))
    )
    (net (code "57") (name "unconnected-(U2-SW-Pad2)") (class "Default")
      (node (ref "U2") (pin "2") (pinfunction "SW_2") (pintype "unspecified+no_connect"))
    )
    (net (code "58") (name "unconnected-(U3-EPAD-Pad13)") (class "Default")
      (node (ref "U3") (pin "13") (pinfunction "EPAD_13") (pintype "no_connect"))
    )
    (net (code "59") (name "unconnected-(U5-NC-Pad7)") (class "Default")
      (node (ref "U5") (pin "7") (pinfunction "NC_7") (pintype "unspecified+no_connect"))
    )
    (net (code "60") (name "unconnected-(U5-NC-Pad14)") (class "Default")
      (node (ref "U5") (pin "14") (pinfunction "NC_14") (pintype "unspecified+no_connect"))
    )
    (net (code "61") (name "unconnected-(U6-IO1-Pad39)") (class "Default")
      (node (ref "U6") (pin "39") (pinfunction "IO1_39") (pintype "unspecified"))
    )
    (net (code "62") (name "unconnected-(U6-IO2-Pad38)") (class "Default")
      (node (ref "U6") (pin "38") (pinfunction "IO2_38") (pintype "unspecified"))
    )
    (net (code "63") (name "unconnected-(U6-IO9-Pad17)") (class "Default")
      (node (ref "U6") (pin "17") (pinfunction "IO9_17") (pintype "unspecified"))
    )
    (net (code "64") (name "unconnected-(U6-IO10-Pad18)") (class "Default")
      (node (ref "U6") (pin "18") (pinfunction "IO10_18") (pintype "unspecified"))
    )
    (net (code "65") (name "unconnected-(U6-IO12-Pad20)") (class "Default")
      (node (ref "U6") (pin "20") (pinfunction "IO12_20") (pintype "unspecified"))
    )
    (net (code "66") (name "unconnected-(U6-IO13-Pad21)") (class "Default")
      (node (ref "U6") (pin "21") (pinfunction "IO13_21") (pintype "unspecified"))
    )
    (net (code "67") (name "unconnected-(U6-IO14-Pad22)") (class "Default")
      (node (ref "U6") (pin "22") (pinfunction "IO14_22") (pintype "unspecified"))
    )
    (net (code "68") (name "unconnected-(U6-IO18-Pad11)") (class "Default")
      (node (ref "U6") (pin "11") (pinfunction "IO18_11") (pintype "unspecified"))
    )
    (net (code "69") (name "unconnected-(U6-IO19-Pad13)") (class "Default")
      (node (ref "U6") (pin "13") (pinfunction "IO19_13") (pintype "unspecified"))
    )
    (net (code "70") (name "unconnected-(U6-IO20-Pad14)") (class "Default")
      (node (ref "U6") (pin "14") (pinfunction "IO20_14") (pintype "unspecified"))
    )
    (net (code "71") (name "unconnected-(U6-IO21-Pad23)") (class "Default")
      (node (ref "U6") (pin "23") (pinfunction "IO21_23") (pintype "unspecified"))
    )
    (net (code "72") (name "unconnected-(U6-IO35-Pad28)") (class "Default")
      (node (ref "U6") (pin "28") (pinfunction "IO35_28") (pintype "unspecified+no_connect"))
    )
    (net (code "73") (name "unconnected-(U6-IO36-Pad29)") (class "Default")
      (node (ref "U6") (pin "29") (pinfunction "IO36_29") (pintype "unspecified+no_connect"))
    )
    (net (code "74") (name "unconnected-(U6-IO37-Pad30)") (class "Default")
      (node (ref "U6") (pin "30") (pinfunction "IO37_30") (pintype "unspecified+no_connect"))
    )
    (net (code "75") (name "unconnected-(U6-IO40-Pad33)") (class "Default")
      (node (ref "U6") (pin "33") (pinfunction "IO40_33") (pintype "unspecified+no_connect"))
    )
    (net (code "76") (name "unconnected-(U6-IO45-Pad26)") (class "Default")
      (node (ref "U6") (pin "26") (pinfunction "IO45_26") (pintype "unspecified"))
    )
    (net (code "77") (name "unconnected-(U6-IO46-Pad16)") (class "Default")
      (node (ref "U6") (pin "16") (pinfunction "IO46_16") (pintype "unspecified+no_connect"))
    )
    (net (code "78") (name "unconnected-(U6-IO47-Pad24)") (class "Default")
      (node (ref "U6") (pin "24") (pinfunction "IO47_24") (pintype "unspecified"))
    )
    (net (code "79") (name "unconnected-(U6-IO48-Pad25)") (class "Default")
      (node (ref "U6") (pin "25") (pinfunction "IO48_25") (pintype "unspecified"))
    )
    (net (code "80") (name "unconnected-(U15-NC-Pad2)") (class "Default")
      (node (ref "U15") (pin "2") (pinfunction "NC_2") (pintype "unspecified+no_connect"))
    )
    (net (code "81") (name "unconnected-(U15-NC-Pad3)") (class "Default")
      (node (ref "U15") (pin "3") (pinfunction "NC_3") (pintype "unspecified+no_connect"))
    )
    (net (code "82") (name "unconnected-(U15-NC-Pad5)") (class "Default")
      (node (ref "U15") (pin "5") (pinfunction "NC_5") (pintype "unspecified+no_connect"))
    )
    (net (code "83") (name "unconnected-(U15-NC-Pad6)") (class "Default")
      (node (ref "U15") (pin "6") (pinfunction "NC_6") (pintype "unspecified+no_connect"))
    )
    (net (code "84") (name "unconnected-(U15-NC-Pad7)") (class "Default")
      (node (ref "U15") (pin "7") (pinfunction "NC_7") (pintype "unspecified+no_connect"))
    )
  )
)
